# jit_pcb_dip.net
KiCad netlist of a schematic drawn in EAGLE
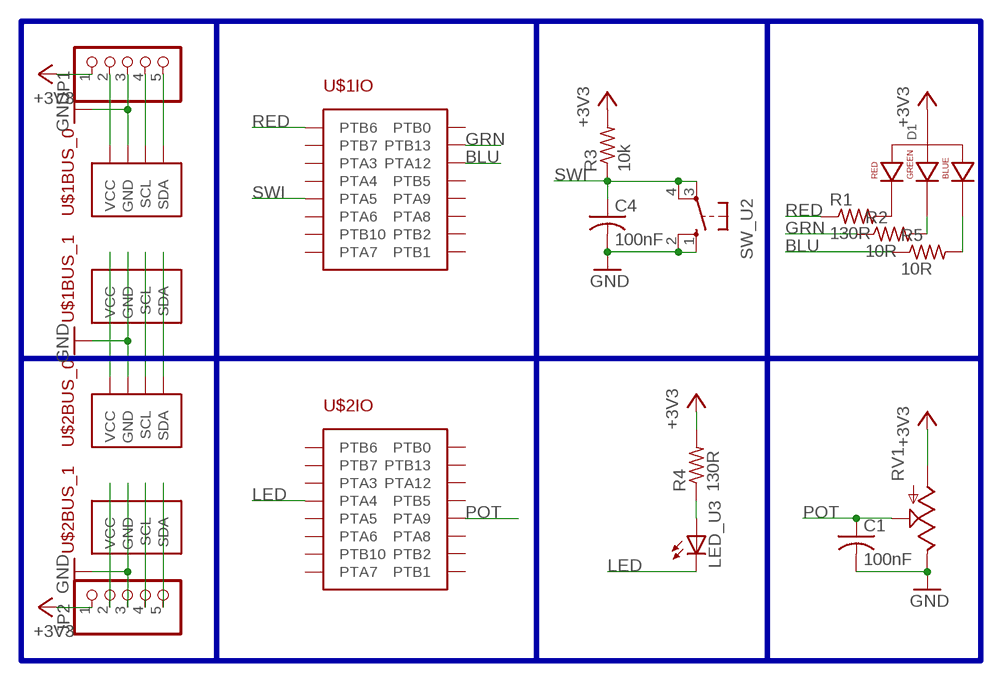
[diagram p0: schematic, sheet 1]

(export (version "E")
  (design (tool "Eeschema 10.0.6"))
  (components
    (comp (ref "C1")
      (value "100nF")
      (footprint "eagle-import:C025-025X050")
      (libsource (lib "eagle-import") (part "C-US025-025X050"))
    )
    (comp (ref "C4")
      (value "100nF")
      (footprint "eagle-import:C025-025X050")
      (libsource (lib "eagle-import") (part "C-US025-025X050"))
    )
    (comp (ref "D1")
      (value "LED-RGB-CA-THRUDIFFUSE")
      (footprint "eagle-import:LED-RGB-THRU")
      (libsource (lib "eagle-import") (part "LED-RGB-CA-THRUDIFFUSE"))
    )
    (comp (ref "JP1")
      (value "PINHD-1X5")
      (footprint "eagle-import:1X05")
      (libsource (lib "eagle-import") (part "PINHD-1X5"))
    )
    (comp (ref "JP2")
      (value "PINHD-1X5")
      (footprint "eagle-import:1X05")
      (libsource (lib "eagle-import") (part "PINHD-1X5"))
    )
    (comp (ref "LED_U3")
      (value "LED5MM")
      (footprint "eagle-import:LED5MM")
      (libsource (lib "eagle-import") (part "LED5MM"))
    )
    (comp (ref "R1")
      (value "130R")
      (footprint "eagle-import:0204_7")
      (libsource (lib "eagle-import") (part "R-US_0204/7"))
    )
    (comp (ref "R2")
      (value "10R")
      (footprint "eagle-import:0204_7")
      (libsource (lib "eagle-import") (part "R-US_0204/7"))
    )
    (comp (ref "R3")
      (value "10k")
      (footprint "eagle-import:0204_7")
      (libsource (lib "eagle-import") (part "R-US_0204/7"))
    )
    (comp (ref "R4")
      (value "130R")
      (footprint "eagle-import:0204_7")
      (libsource (lib "eagle-import") (part "R-US_0204/7"))
    )
    (comp (ref "R5")
      (value "10R")
      (footprint "eagle-import:0204_7")
      (libsource (lib "eagle-import") (part "R-US_0204/7"))
    )
    (comp (ref "RV1")
      (value "POT100K_3362U")
      (footprint "eagle-import:3362U")
      (libsource (lib "eagle-import") (part "POT100K_3362U"))
    )
    (comp (ref "SW_U2")
      (value "10-XX")
      (footprint "eagle-import:B3F-10XX")
      (fields (field (name "MPN") "B3F-1000"))
      (libsource (lib "eagle-import") (part "10-XX"))
    )
    (comp (ref "U$1")
      (value "MODROB_CARRIER-DIP")
      (footprint "eagle-import:CARRIER_DIP")
      (libsource (lib "eagle-import") (part "MODROB_CARRIER-DIP"))
    )
    (comp (ref "U$2")
      (value "MODROB_CARRIER-DIP")
      (footprint "eagle-import:CARRIER_DIP")
      (libsource (lib "eagle-import") (part "MODROB_CARRIER-DIP"))
    )
  )
  (nets
    (net (code "1") (name "+3V3") (class "Default")
      (node (ref "D1") (pin "2") (pinfunction "ANODE_2") (pintype "bidirectional"))
      (node (ref "JP1") (pin "1") (pinfunction "1_1") (pintype "passive"))
      (node (ref "JP2") (pin "1") (pinfunction "1_1") (pintype "passive"))
      (node (ref "R3") (pin "2") (pinfunction "2_2") (pintype "passive"))
      (node (ref "R4") (pin "2") (pinfunction "2_2") (pintype "passive"))
      (node (ref "RV1") (pin "P$3") (pinfunction "A_P$3") (pintype "passive"))
    )
    (net (code "2") (name "/BLU") (class "Default")
      (node (ref "R5") (pin "1") (pinfunction "1_1") (pintype "passive"))
      (node (ref "U$1") (pin "PTA12") (pinfunction "PTA12_PTA12") (pintype "bidirectional"))
    )
    (net (code "3") (name "/GRN") (class "Default")
      (node (ref "R2") (pin "1") (pinfunction "1_1") (pintype "passive"))
      (node (ref "U$1") (pin "PTB13") (pinfunction "PTB13_PTB13") (pintype "bidirectional"))
    )
    (net (code "4") (name "/LED") (class "Default")
      (node (ref "LED_U3") (pin "K") (pinfunction "C_K") (pintype "passive"))
      (node (ref "U$2") (pin "PTA4") (pinfunction "PTA4_PTA4") (pintype "bidirectional"))
    )
    (net (code "5") (name "/POT") (class "Default")
      (node (ref "C1") (pin "1") (pinfunction "1_1") (pintype "passive"))
      (node (ref "RV1") (pin "P$2") (pinfunction "S_P$2") (pintype "passive"))
      (node (ref "U$2") (pin "PTA9") (pinfunction "PTA9_PTA9") (pintype "bidirectional"))
    )
    (net (code "6") (name "/RED") (class "Default")
      (node (ref "R1") (pin "1") (pinfunction "1_1") (pintype "passive"))
      (node (ref "U$1") (pin "PTB6") (pinfunction "PTB6_PTB6") (pintype "bidirectional"))
    )
    (net (code "7") (name "/SWI") (class "Default")
      (node (ref "C4") (pin "1") (pinfunction "1_1") (pintype "passive"))
      (node (ref "R3") (pin "1") (pinfunction "1_1") (pintype "passive"))
      (node (ref "SW_U2") (pin "3") (pinfunction "P_3") (pintype "passive"))
      (node (ref "SW_U2") (pin "4") (pinfunction "P1_4") (pintype "passive"))
      (node (ref "U$1") (pin "PTA5") (pinfunction "PTA5_PTA5") (pintype "bidirectional"))
    )
    (net (code "8") (name "GND") (class "Default")
      (node (ref "C1") (pin "2") (pinfunction "2_2") (pintype "passive"))
      (node (ref "C4") (pin "2") (pinfunction "2_2") (pintype "passive"))
      (node (ref "JP1") (pin "3") (pinfunction "3_3") (pintype "passive"))
      (node (ref "JP2") (pin "3") (pinfunction "3_3") (pintype "passive"))
      (node (ref "RV1") (pin "P$1") (pinfunction "E_P$1") (pintype "passive"))
      (node (ref "SW_U2") (pin "1") (pinfunction "S_1") (pintype "passive"))
      (node (ref "SW_U2") (pin "2") (pinfunction "S1_2") (pintype "passive"))
      (node (ref "U$1") (pin "GND_0") (pinfunction "GND_GND_0") (pintype "bidirectional"))
      (node (ref "U$1") (pin "GND_1") (pinfunction "GND_GND_1") (pintype "bidirectional"))
      (node (ref "U$2") (pin "GND_0") (pinfunction "GND_GND_0") (pintype "bidirectional"))
      (node (ref "U$2") (pin "GND_1") (pinfunction "GND_GND_1") (pintype "bidirectional"))
    )
    (net (code "9") (name "Net-(D1-BLUE_CATHODE)") (class "Default")
      (node (ref "D1") (pin "4") (pinfunction "BLUE_CATHODE_4") (pintype "bidirectional"))
      (node (ref "R5") (pin "2") (pinfunction "2_2") (pintype "passive"))
    )
    (net (code "10") (name "Net-(D1-GREEN_CATHODE)") (class "Default")
      (node (ref "D1") (pin "3") (pinfunction "GREEN_CATHODE_3") (pintype "bidirectional"))
      (node (ref "R2") (pin "2") (pinfunction "2_2") (pintype "passive"))
    )
    (net (code "11") (name "Net-(D1-RED_CATHODE)") (class "Default")
      (node (ref "D1") (pin "1") (pinfunction "RED_CATHODE_1") (pintype "bidirectional"))
      (node (ref "R1") (pin "2") (pinfunction "2_2") (pintype "passive"))
    )
    (net (code "12") (name "Net-(LED_U3-PadA)") (class "Default")
      (node (ref "LED_U3") (pin "A") (pinfunction "A_A") (pintype "passive"))
      (node (ref "R4") (pin "1") (pinfunction "1_1") (pintype "passive"))
    )
    (net (code "13") (name "Net-(U$1A-SCL)") (class "Default")
      (node (ref "JP1") (pin "4") (pinfunction "4_4") (pintype "passive"))
      (node (ref "U$1") (pin "SCL_0") (pinfunction "SCL_SCL_0") (pintype "bidirectional"))
    )
    (net (code "14") (name "Net-(U$1A-SDA)") (class "Default")
      (node (ref "JP1") (pin "5") (pinfunction "5_5") (pintype "passive"))
      (node (ref "U$1") (pin "SDA_0") (pinfunction "SDA_SDA_0") (pintype "bidirectional"))
    )
    (net (code "15") (name "Net-(U$1A-VCC)") (class "Default")
      (node (ref "JP1") (pin "2") (pinfunction "2_2") (pintype "passive"))
      (node (ref "U$1") (pin "VCC_0") (pinfunction "VCC_VCC_0") (pintype "bidirectional"))
    )
    (net (code "16") (name "Net-(U$1B-SCL)") (class "Default")
      (node (ref "U$1") (pin "SCL_1") (pinfunction "SCL_SCL_1") (pintype "bidirectional"))
      (node (ref "U$2") (pin "SCL_0") (pinfunction "SCL_SCL_0") (pintype "bidirectional"))
    )
    (net (code "17") (name "Net-(U$1B-SDA)") (class "Default")
      (node (ref "U$1") (pin "SDA_1") (pinfunction "SDA_SDA_1") (pintype "bidirectional"))
      (node (ref "U$2") (pin "SDA_0") (pinfunction "SDA_SDA_0") (pintype "bidirectional"))
    )
    (net (code "18") (name "Net-(U$1B-VCC)") (class "Default")
      (node (ref "U$1") (pin "VCC_1") (pinfunction "VCC_VCC_1") (pintype "bidirectional"))
      (node (ref "U$2") (pin "VCC_0") (pinfunction "VCC_VCC_0") (pintype "bidirectional"))
    )
    (net (code "19") (name "Net-(U$2B-SCL)") (class "Default")
      (node (ref "JP2") (pin "4") (pinfunction "4_4") (pintype "passive"))
      (node (ref "U$2") (pin "SCL_1") (pinfunction "SCL_SCL_1") (pintype "bidirectional"))
    )
    (net (code "20") (name "Net-(U$2B-SDA)") (class "Default")
      (node (ref "JP2") (pin "5") (pinfunction "5_5") (pintype "passive"))
      (node (ref "U$2") (pin "SDA_1") (pinfunction "SDA_SDA_1") (pintype "bidirectional"))
    )
    (net (code "21") (name "Net-(U$2B-VCC)") (class "Default")
      (node (ref "JP2") (pin "2") (pinfunction "2_2") (pintype "passive"))
      (node (ref "U$2") (pin "VCC_1") (pinfunction "VCC_VCC_1") (pintype "bidirectional"))
    )
    (net (code "22") (name "unconnected-(U$1-PadPTA3)") (class "Default")
      (node (ref "U$1") (pin "PTA3") (pinfunction "PTA3_PTA3") (pintype "bidirectional"))
    )
    (net (code "23") (name "unconnected-(U$1-PadPTA4)") (class "Default")
      (node (ref "U$1") (pin "PTA4") (pinfunction "PTA4_PTA4") (pintype "bidirectional"))
    )
    (net (code "24") (name "unconnected-(U$1-PadPTA6)") (class "Default")
      (node (ref "U$1") (pin "PTA6") (pinfunction "PTA6_PTA6") (pintype "bidirectional"))
    )
    (net (code "25") (name "unconnected-(U$1-PadPTA7)") (class "Default")
      (node (ref "U$1") (pin "PTA7") (pinfunction "PTA7_PTA7") (pintype "bidirectional"))
    )
    (net (code "26") (name "unconnected-(U$1-PadPTA8)") (class "Default")
      (node (ref "U$1") (pin "PTA8") (pinfunction "PTA8_PTA8") (pintype "bidirectional"))
    )
    (net (code "27") (name "unconnected-(U$1-PadPTA9)") (class "Default")
      (node (ref "U$1") (pin "PTA9") (pinfunction "PTA9_PTA9") (pintype "bidirectional"))
    )
    (net (code "28") (name "unconnected-(U$1-PadPTB0)") (class "Default")
      (node (ref "U$1") (pin "PTB0") (pinfunction "PTB0_PTB0") (pintype "bidirectional"))
    )
    (net (code "29") (name "unconnected-(U$1-PadPTB1)") (class "Default")
      (node (ref "U$1") (pin "PTB1") (pinfunction "PTB1_PTB1") (pintype "bidirectional"))
    )
    (net (code "30") (name "unconnected-(U$1-PadPTB2)") (class "Default")
      (node (ref "U$1") (pin "PTB2") (pinfunction "PTB2_PTB2") (pintype "bidirectional"))
    )
    (net (code "31") (name "unconnected-(U$1-PadPTB5)") (class "Default")
      (node (ref "U$1") (pin "PTB5") (pinfunction "PTB5_PTB5") (pintype "bidirectional"))
    )
    (net (code "32") (name "unconnected-(U$1-PadPTB7)") (class "Default")
      (node (ref "U$1") (pin "PTB7") (pinfunction "PTB7_PTB7") (pintype "bidirectional"))
    )
    (net (code "33") (name "unconnected-(U$1-PadPTB10)") (class "Default")
      (node (ref "U$1") (pin "PTB10") (pinfunction "PTB10_PTB10") (pintype "bidirectional"))
    )
    (net (code "34") (name "unconnected-(U$2-PadPTA3)") (class "Default")
      (node (ref "U$2") (pin "PTA3") (pinfunction "PTA3_PTA3") (pintype "bidirectional"))
    )
    (net (code "35") (name "unconnected-(U$2-PadPTA5)") (class "Default")
      (node (ref "U$2") (pin "PTA5") (pinfunction "PTA5_PTA5") (pintype "bidirectional"))
    )
    (net (code "36") (name "unconnected-(U$2-PadPTA6)") (class "Default")
      (node (ref "U$2") (pin "PTA6") (pinfunction "PTA6_PTA6") (pintype "bidirectional"))
    )
    (net (code "37") (name "unconnected-(U$2-PadPTA7)") (class "Default")
      (node (ref "U$2") (pin "PTA7") (pinfunction "PTA7_PTA7") (pintype "bidirectional"))
    )
    (net (code "38") (name "unconnected-(U$2-PadPTA8)") (class "Default")
      (node (ref "U$2") (pin "PTA8") (pinfunction "PTA8_PTA8") (pintype "bidirectional"))
    )
    (net (code "39") (name "unconnected-(U$2-PadPTA12)") (class "Default")
      (node (ref "U$2") (pin "PTA12") (pinfunction "PTA12_PTA12") (pintype "bidirectional"))
    )
    (net (code "40") (name "unconnected-(U$2-PadPTB0)") (class "Default")
      (node (ref "U$2") (pin "PTB0") (pinfunction "PTB0_PTB0") (pintype "bidirectional"))
    )
    (net (code "41") (name "unconnected-(U$2-PadPTB1)") (class "Default")
      (node (ref "U$2") (pin "PTB1") (pinfunction "PTB1_PTB1") (pintype "bidirectional"))
    )
    (net (code "42") (name "unconnected-(U$2-PadPTB2)") (class "Default")
      (node (ref "U$2") (pin "PTB2") (pinfunction "PTB2_PTB2") (pintype "bidirectional"))
    )
    (net (code "43") (name "unconnected-(U$2-PadPTB5)") (class "Default")
      (node (ref "U$2") (pin "PTB5") (pinfunction "PTB5_PTB5") (pintype "bidirectional"))
    )
    (net (code "44") (name "unconnected-(U$2-PadPTB6)") (class "Default")
      (node (ref "U$2") (pin "PTB6") (pinfunction "PTB6_PTB6") (pintype "bidirectional"))
    )
    (net (code "45") (name "unconnected-(U$2-PadPTB7)") (class "Default")
      (node (ref "U$2") (pin "PTB7") (pinfunction "PTB7_PTB7") (pintype "bidirectional"))
    )
    (net (code "46") (name "unconnected-(U$2-PadPTB10)") (class "Default")
      (node (ref "U$2") (pin "PTB10") (pinfunction "PTB10_PTB10") (pintype "bidirectional"))
    )
    (net (code "47") (name "unconnected-(U$2-PadPTB13)") (class "Default")
      (node (ref "U$2") (pin "PTB13") (pinfunction "PTB13_PTB13") (pintype "bidirectional"))
    )
  )
)
